# USB2USB.net
KiCad netlist of a schematic drawn in Altium Designer
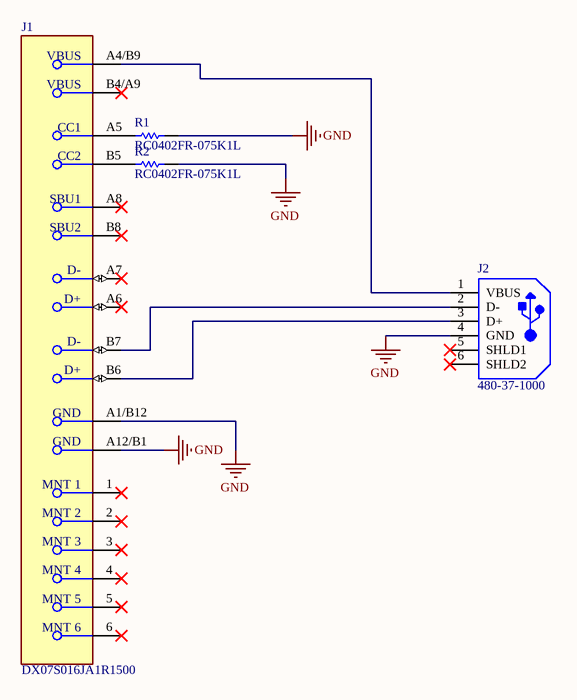
[diagram p0: USB2USB.SchDoc]

(export (version "E")
  (design (tool "Eeschema 10.0.6"))
  (components
    (comp (ref "J1")
      (value "DX07S016JA1R1500")
      (footprint "FP-DX07S016JA1R1500-MFG")
      (description "CONN RCP USB2.0 TYP C 24P SMD RA")
      (libsource (lib "Altium Content Vault") (part "7f3e9989102a0f22bff9cb010881d34"))
    )
    (comp (ref "J2")
      (value "480-37-1000")
      (footprint "MOLX-480-37-1000_V")
      (fields (field (name "TOLERANCE") "1%"))
      (libsource (lib "Altium Content Vault") (part "USB-4-2SHLD"))
    )
    (comp (ref "R1")
      (value "RC0402FR-075K1L")
      (footprint "RESC1005X40X25NL05T10")
      (fields (field (name "MANUFACTURER") "Yageo / Phycomp"))
      (libsource (lib "Altium Content Vault") (part "RES"))
    )
    (comp (ref "R2")
      (value "RC0402FR-075K1L")
      (footprint "RESC1005X40X25NL05T10")
      (fields (field (name "MANUFACTURER") "Yageo / Phycomp"))
      (libsource (lib "Altium Content Vault") (part "RES"))
    )
  )
  (nets
    (net (code "1") (name "GND") (class "Default")
      (node (ref "J1") (pin "A1/B12") (pinfunction "GND_A1/B12") (pintype "power_in"))
      (node (ref "J1") (pin "A12/B1") (pinfunction "GND_A12/B1") (pintype "power_in"))
      (node (ref "J2") (pin "4") (pinfunction "GND_4") (pintype "passive"))
      (node (ref "R1") (pin "2") (pinfunction "2_2") (pintype "passive"))
      (node (ref "R2") (pin "2") (pinfunction "2_2") (pintype "passive"))
    )
    (net (code "2") (name "Net-(J1-CC1)") (class "Default")
      (node (ref "J1") (pin "A5") (pinfunction "CC1_A5") (pintype "passive"))
      (node (ref "R1") (pin "1") (pinfunction "1_1") (pintype "passive"))
    )
    (net (code "3") (name "Net-(J1-CC2)") (class "Default")
      (node (ref "J1") (pin "B5") (pinfunction "CC2_B5") (pintype "passive"))
      (node (ref "R2") (pin "1") (pinfunction "1_1") (pintype "passive"))
    )
    (net (code "4") (name "Net-(J2-D+)") (class "Default")
      (node (ref "J1") (pin "B6") (pinfunction "D+_B6") (pintype "bidirectional"))
      (node (ref "J2") (pin "3") (pinfunction "D+_3") (pintype "passive"))
    )
    (net (code "5") (name "Net-(J2-D-)") (class "Default")
      (node (ref "J1") (pin "B7") (pinfunction "D-_B7") (pintype "bidirectional"))
      (node (ref "J2") (pin "2") (pinfunction "D-_2") (pintype "passive"))
    )
    (net (code "6") (name "Net-(J2-VBUS)") (class "Default")
      (node (ref "J1") (pin "A4/B9") (pinfunction "VBUS_A4/B9") (pintype "power_in"))
      (node (ref "J2") (pin "1") (pinfunction "VBUS_1") (pintype "passive"))
    )
    (net (code "7") (name "unconnected-(J1-D+-PadA6)") (class "Default")
      (node (ref "J1") (pin "A6") (pinfunction "D+_A6") (pintype "bidirectional+no_connect"))
    )
    (net (code "8") (name "unconnected-(J1-D--PadA7)") (class "Default")
      (node (ref "J1") (pin "A7") (pinfunction "D-_A7") (pintype "bidirectional+no_connect"))
    )
    (net (code "9") (name "unconnected-(J1-MNT_1-Pad1)") (class "Default")
      (node (ref "J1") (pin "1") (pinfunction "MNT_1_1") (pintype "passive+no_connect"))
    )
    (net (code "10") (name "unconnected-(J1-MNT_2-Pad2)") (class "Default")
      (node (ref "J1") (pin "2") (pinfunction "MNT_2_2") (pintype "passive+no_connect"))
    )
    (net (code "11") (name "unconnected-(J1-MNT_3-Pad3)") (class "Default")
      (node (ref "J1") (pin "3") (pinfunction "MNT_3_3") (pintype "passive+no_connect"))
    )
    (net (code "12") (name "unconnected-(J1-MNT_4-Pad4)") (class "Default")
      (node (ref "J1") (pin "4") (pinfunction "MNT_4_4") (pintype "passive+no_connect"))
    )
    (net (code "13") (name "unconnected-(J1-MNT_5-Pad5)") (class "Default")
      (node (ref "J1") (pin "5") (pinfunction "MNT_5_5") (pintype "passive+no_connect"))
    )
    (net (code "14") (name "unconnected-(J1-MNT_6-Pad6)") (class "Default")
      (node (ref "J1") (pin "6") (pinfunction "MNT_6_6") (pintype "passive+no_connect"))
    )
    (net (code "15") (name "unconnected-(J1-SBU1-PadA8)") (class "Default")
      (node (ref "J1") (pin "A8") (pinfunction "SBU1_A8") (pintype "passive+no_connect"))
    )
    (net (code "16") (name "unconnected-(J1-SBU2-PadB8)") (class "Default")
      (node (ref "J1") (pin "B8") (pinfunction "SBU2_B8") (pintype "passive+no_connect"))
    )
    (net (code "17") (name "unconnected-(J1-VBUS-PadB4{slash}A9)") (class "Default")
      (node (ref "J1") (pin "B4/A9") (pinfunction "VBUS_B4/A9") (pintype "power_in+no_connect"))
    )
    (net (code "18") (name "unconnected-(J2-SHLD1-Pad5)") (class "Default")
      (node (ref "J2") (pin "5") (pinfunction "SHLD1_5") (pintype "passive+no_connect"))
    )
    (net (code "19") (name "unconnected-(J2-SHLD2-Pad6)") (class "Default")
      (node (ref "J2") (pin "6") (pinfunction "SHLD2_6") (pintype "passive+no_connect"))
    )
  )
)
